# SCH_16pady.net
KiCad netlist of a schematic drawn in EasyEDA
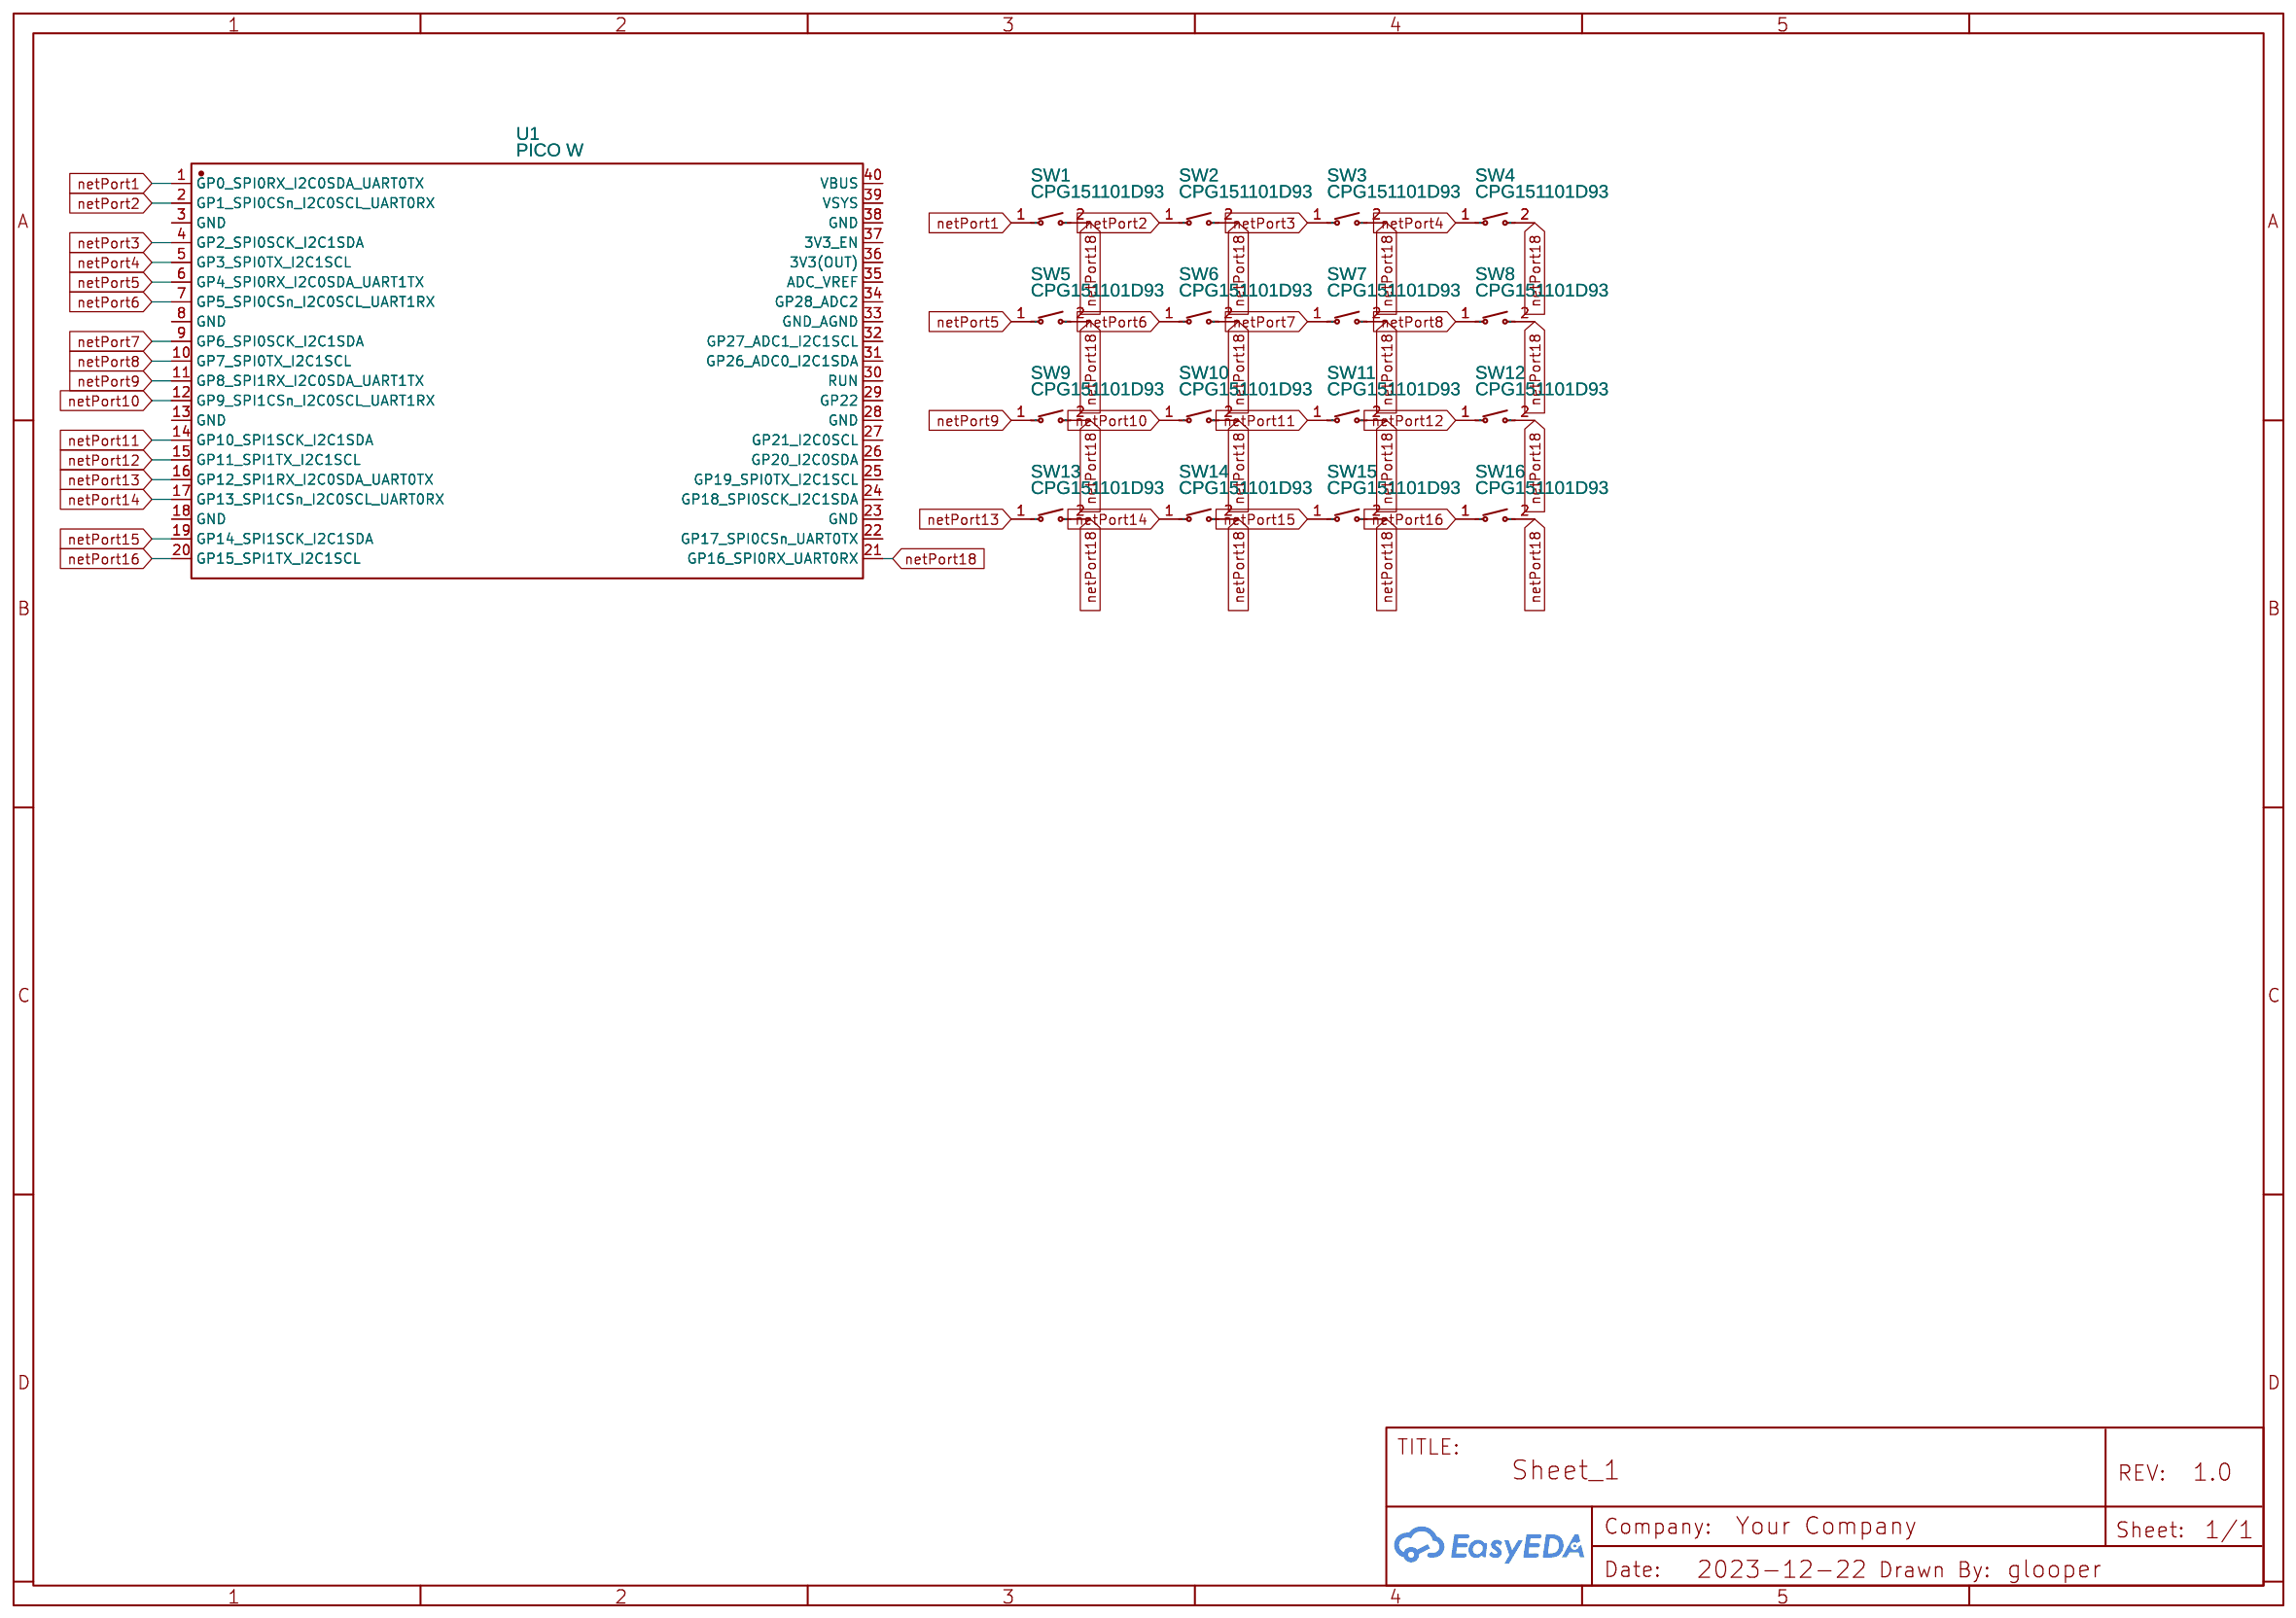
[diagram p0: schematic sheet]

(export (version "E")
  (design (tool "Eeschema 10.0.6"))
  (components
    (comp (ref "SW1")
      (value "CPG151101D93")
      (fields (field (name "Manufacturer") "Kailh(凯华)"))
      (libsource (lib "") (part "CPG151101D93"))
    )
    (comp (ref "SW2")
      (value "CPG151101D93")
      (fields (field (name "Manufacturer") "Kailh(凯华)"))
      (libsource (lib "") (part "CPG151101D93"))
    )
    (comp (ref "SW3")
      (value "CPG151101D93")
      (fields (field (name "Manufacturer") "Kailh(凯华)"))
      (libsource (lib "") (part "CPG151101D93"))
    )
    (comp (ref "SW4")
      (value "CPG151101D93")
      (fields (field (name "Manufacturer") "Kailh(凯华)"))
      (libsource (lib "") (part "CPG151101D93"))
    )
    (comp (ref "SW5")
      (value "CPG151101D93")
      (fields (field (name "Manufacturer") "Kailh(凯华)"))
      (libsource (lib "") (part "CPG151101D93"))
    )
    (comp (ref "SW6")
      (value "CPG151101D93")
      (fields (field (name "Manufacturer") "Kailh(凯华)"))
      (libsource (lib "") (part "CPG151101D93"))
    )
    (comp (ref "SW7")
      (value "CPG151101D93")
      (fields (field (name "Manufacturer") "Kailh(凯华)"))
      (libsource (lib "") (part "CPG151101D93"))
    )
    (comp (ref "SW8")
      (value "CPG151101D93")
      (fields (field (name "Manufacturer") "Kailh(凯华)"))
      (libsource (lib "") (part "CPG151101D93"))
    )
    (comp (ref "SW9")
      (value "CPG151101D93")
      (fields (field (name "Manufacturer") "Kailh(凯华)"))
      (libsource (lib "") (part "CPG151101D93"))
    )
    (comp (ref "SW10")
      (value "CPG151101D93")
      (fields (field (name "Manufacturer") "Kailh(凯华)"))
      (libsource (lib "") (part "CPG151101D93"))
    )
    (comp (ref "SW11")
      (value "CPG151101D93")
      (fields (field (name "Manufacturer") "Kailh(凯华)"))
      (libsource (lib "") (part "CPG151101D93"))
    )
    (comp (ref "SW12")
      (value "CPG151101D93")
      (fields (field (name "Manufacturer") "Kailh(凯华)"))
      (libsource (lib "") (part "CPG151101D93"))
    )
    (comp (ref "SW13")
      (value "CPG151101D93")
      (fields (field (name "Manufacturer") "Kailh(凯华)"))
      (libsource (lib "") (part "CPG151101D93"))
    )
    (comp (ref "SW14")
      (value "CPG151101D93")
      (fields (field (name "Manufacturer") "Kailh(凯华)"))
      (libsource (lib "") (part "CPG151101D93"))
    )
    (comp (ref "SW15")
      (value "CPG151101D93")
      (fields (field (name "Manufacturer") "Kailh(凯华)"))
      (libsource (lib "") (part "CPG151101D93"))
    )
    (comp (ref "SW16")
      (value "CPG151101D93")
      (fields (field (name "Manufacturer") "Kailh(凯华)"))
      (libsource (lib "") (part "CPG151101D93"))
    )
    (comp (ref "U1")
      (value "PICO W")
      (fields (field (name "Manufacturer") "Raspberry Pi(树莓派)"))
      (libsource (lib "") (part "PICO W"))
    )
  )
  (nets
    (net (code "1") (name "netPort1") (class "Default")
      (node (ref "SW1") (pin "1") (pinfunction "1_1") (pintype "unspecified"))
      (node (ref "U1") (pin "1") (pinfunction "GP0_SPI0RX_I2C0SDA_UART0TX_1") (pintype "unspecified"))
    )
    (net (code "2") (name "netPort2") (class "Default")
      (node (ref "SW2") (pin "1") (pinfunction "1_1") (pintype "unspecified"))
      (node (ref "U1") (pin "2") (pinfunction "GP1_SPI0CSn_I2C0SCL_UART0RX_2") (pintype "unspecified"))
    )
    (net (code "3") (name "netPort3") (class "Default")
      (node (ref "SW3") (pin "1") (pinfunction "1_1") (pintype "unspecified"))
      (node (ref "U1") (pin "4") (pinfunction "GP2_SPI0SCK_I2C1SDA_4") (pintype "unspecified"))
    )
    (net (code "4") (name "netPort4") (class "Default")
      (node (ref "SW4") (pin "1") (pinfunction "1_1") (pintype "unspecified"))
      (node (ref "U1") (pin "5") (pinfunction "GP3_SPI0TX_I2C1SCL_5") (pintype "unspecified"))
    )
    (net (code "5") (name "netPort5") (class "Default")
      (node (ref "SW5") (pin "1") (pinfunction "1_1") (pintype "unspecified"))
      (node (ref "U1") (pin "6") (pinfunction "GP4_SPI0RX_I2C0SDA_UART1TX_6") (pintype "unspecified"))
    )
    (net (code "6") (name "netPort6") (class "Default")
      (node (ref "SW6") (pin "1") (pinfunction "1_1") (pintype "unspecified"))
      (node (ref "U1") (pin "7") (pinfunction "GP5_SPI0CSn_I2C0SCL_UART1RX_7") (pintype "unspecified"))
    )
    (net (code "7") (name "netPort7") (class "Default")
      (node (ref "SW7") (pin "1") (pinfunction "1_1") (pintype "unspecified"))
      (node (ref "U1") (pin "9") (pinfunction "GP6_SPI0SCK_I2C1SDA_9") (pintype "unspecified"))
    )
    (net (code "8") (name "netPort8") (class "Default")
      (node (ref "SW8") (pin "1") (pinfunction "1_1") (pintype "unspecified"))
      (node (ref "U1") (pin "10") (pinfunction "GP7_SPI0TX_I2C1SCL_10") (pintype "unspecified"))
    )
    (net (code "9") (name "netPort9") (class "Default")
      (node (ref "SW9") (pin "1") (pinfunction "1_1") (pintype "unspecified"))
      (node (ref "U1") (pin "11") (pinfunction "GP8_SPI1RX_I2C0SDA_UART1TX_11") (pintype "unspecified"))
    )
    (net (code "10") (name "netPort10") (class "Default")
      (node (ref "SW10") (pin "1") (pinfunction "1_1") (pintype "unspecified"))
      (node (ref "U1") (pin "12") (pinfunction "GP9_SPI1CSn_I2C0SCL_UART1RX_12") (pintype "unspecified"))
    )
    (net (code "11") (name "netPort11") (class "Default")
      (node (ref "SW11") (pin "1") (pinfunction "1_1") (pintype "unspecified"))
      (node (ref "U1") (pin "14") (pinfunction "GP10_SPI1SCK_I2C1SDA_14") (pintype "unspecified"))
    )
    (net (code "12") (name "netPort12") (class "Default")
      (node (ref "SW12") (pin "1") (pinfunction "1_1") (pintype "unspecified"))
      (node (ref "U1") (pin "15") (pinfunction "GP11_SPI1TX_I2C1SCL_15") (pintype "unspecified"))
    )
    (net (code "13") (name "netPort13") (class "Default")
      (node (ref "SW13") (pin "1") (pinfunction "1_1") (pintype "unspecified"))
      (node (ref "U1") (pin "16") (pinfunction "GP12_SPI1RX_I2C0SDA_UART0TX_16") (pintype "unspecified"))
    )
    (net (code "14") (name "netPort14") (class "Default")
      (node (ref "SW14") (pin "1") (pinfunction "1_1") (pintype "unspecified"))
      (node (ref "U1") (pin "17") (pinfunction "GP13_SPI1CSn_I2C0SCL_UART0RX_17") (pintype "unspecified"))
    )
    (net (code "15") (name "netPort15") (class "Default")
      (node (ref "SW15") (pin "1") (pinfunction "1_1") (pintype "unspecified"))
      (node (ref "U1") (pin "19") (pinfunction "GP14_SPI1SCK_I2C1SDA_19") (pintype "unspecified"))
    )
    (net (code "16") (name "netPort16") (class "Default")
      (node (ref "SW16") (pin "1") (pinfunction "1_1") (pintype "unspecified"))
      (node (ref "U1") (pin "20") (pinfunction "GP15_SPI1TX_I2C1SCL_20") (pintype "unspecified"))
    )
    (net (code "17") (name "netPort18") (class "Default")
      (node (ref "SW1") (pin "2") (pinfunction "2_2") (pintype "unspecified"))
      (node (ref "SW10") (pin "2") (pinfunction "2_2") (pintype "unspecified"))
      (node (ref "SW11") (pin "2") (pinfunction "2_2") (pintype "unspecified"))
      (node (ref "SW12") (pin "2") (pinfunction "2_2") (pintype "unspecified"))
      (node (ref "SW13") (pin "2") (pinfunction "2_2") (pintype "unspecified"))
      (node (ref "SW14") (pin "2") (pinfunction "2_2") (pintype "unspecified"))
      (node (ref "SW15") (pin "2") (pinfunction "2_2") (pintype "unspecified"))
      (node (ref "SW16") (pin "2") (pinfunction "2_2") (pintype "unspecified"))
      (node (ref "SW2") (pin "2") (pinfunction "2_2") (pintype "unspecified"))
      (node (ref "SW3") (pin "2") (pinfunction "2_2") (pintype "unspecified"))
      (node (ref "SW4") (pin "2") (pinfunction "2_2") (pintype "unspecified"))
      (node (ref "SW5") (pin "2") (pinfunction "2_2") (pintype "unspecified"))
      (node (ref "SW6") (pin "2") (pinfunction "2_2") (pintype "unspecified"))
      (node (ref "SW7") (pin "2") (pinfunction "2_2") (pintype "unspecified"))
      (node (ref "SW8") (pin "2") (pinfunction "2_2") (pintype "unspecified"))
      (node (ref "SW9") (pin "2") (pinfunction "2_2") (pintype "unspecified"))
      (node (ref "U1") (pin "21") (pinfunction "GP16_SPI0RX_UART0RX_21") (pintype "unspecified"))
    )
    (net (code "18") (name "unconnected-(U1-3V3(OUT)-Pad36)") (class "Default")
      (node (ref "U1") (pin "36") (pinfunction "3V3(OUT)_36") (pintype "unspecified"))
    )
    (net (code "19") (name "unconnected-(U1-3V3_EN-Pad37)") (class "Default")
      (node (ref "U1") (pin "37") (pinfunction "3V3_EN_37") (pintype "unspecified"))
    )
    (net (code "20") (name "unconnected-(U1-ADC_VREF-Pad35)") (class "Default")
      (node (ref "U1") (pin "35") (pinfunction "ADC_VREF_35") (pintype "unspecified"))
    )
    (net (code "21") (name "unconnected-(U1-GND-Pad3)") (class "Default")
      (node (ref "U1") (pin "3") (pinfunction "GND_3") (pintype "unspecified"))
    )
    (net (code "22") (name "unconnected-(U1-GND-Pad8)") (class "Default")
      (node (ref "U1") (pin "8") (pinfunction "GND_8") (pintype "unspecified"))
    )
    (net (code "23") (name "unconnected-(U1-GND-Pad13)") (class "Default")
      (node (ref "U1") (pin "13") (pinfunction "GND_13") (pintype "unspecified"))
    )
    (net (code "24") (name "unconnected-(U1-GND-Pad18)") (class "Default")
      (node (ref "U1") (pin "18") (pinfunction "GND_18") (pintype "unspecified"))
    )
    (net (code "25") (name "unconnected-(U1-GND-Pad23)") (class "Default")
      (node (ref "U1") (pin "23") (pinfunction "GND_23") (pintype "unspecified"))
    )
    (net (code "26") (name "unconnected-(U1-GND-Pad28)") (class "Default")
      (node (ref "U1") (pin "28") (pinfunction "GND_28") (pintype "unspecified"))
    )
    (net (code "27") (name "unconnected-(U1-GND-Pad38)") (class "Default")
      (node (ref "U1") (pin "38") (pinfunction "GND_38") (pintype "unspecified"))
    )
    (net (code "28") (name "unconnected-(U1-GND_AGND-Pad33)") (class "Default")
      (node (ref "U1") (pin "33") (pinfunction "GND_AGND_33") (pintype "unspecified"))
    )
    (net (code "29") (name "unconnected-(U1-GP17_SPI0CSn_UART0TX-Pad22)") (class "Default")
      (node (ref "U1") (pin "22") (pinfunction "GP17_SPI0CSn_UART0TX_22") (pintype "unspecified"))
    )
    (net (code "30") (name "unconnected-(U1-GP18_SPI0SCK_I2C1SDA-Pad24)") (class "Default")
      (node (ref "U1") (pin "24") (pinfunction "GP18_SPI0SCK_I2C1SDA_24") (pintype "unspecified"))
    )
    (net (code "31") (name "unconnected-(U1-GP19_SPI0TX_I2C1SCL-Pad25)") (class "Default")
      (node (ref "U1") (pin "25") (pinfunction "GP19_SPI0TX_I2C1SCL_25") (pintype "unspecified"))
    )
    (net (code "32") (name "unconnected-(U1-GP20_I2C0SDA-Pad26)") (class "Default")
      (node (ref "U1") (pin "26") (pinfunction "GP20_I2C0SDA_26") (pintype "unspecified"))
    )
    (net (code "33") (name "unconnected-(U1-GP21_I2C0SCL-Pad27)") (class "Default")
      (node (ref "U1") (pin "27") (pinfunction "GP21_I2C0SCL_27") (pintype "unspecified"))
    )
    (net (code "34") (name "unconnected-(U1-GP22-Pad29)") (class "Default")
      (node (ref "U1") (pin "29") (pinfunction "GP22_29") (pintype "unspecified"))
    )
    (net (code "35") (name "unconnected-(U1-GP26_ADC0_I2C1SDA-Pad31)") (class "Default")
      (node (ref "U1") (pin "31") (pinfunction "GP26_ADC0_I2C1SDA_31") (pintype "unspecified"))
    )
    (net (code "36") (name "unconnected-(U1-GP27_ADC1_I2C1SCL-Pad32)") (class "Default")
      (node (ref "U1") (pin "32") (pinfunction "GP27_ADC1_I2C1SCL_32") (pintype "unspecified"))
    )
    (net (code "37") (name "unconnected-(U1-GP28_ADC2-Pad34)") (class "Default")
      (node (ref "U1") (pin "34") (pinfunction "GP28_ADC2_34") (pintype "unspecified"))
    )
    (net (code "38") (name "unconnected-(U1-RUN-Pad30)") (class "Default")
      (node (ref "U1") (pin "30") (pinfunction "RUN_30") (pintype "unspecified"))
    )
    (net (code "39") (name "unconnected-(U1-VBUS-Pad40)") (class "Default")
      (node (ref "U1") (pin "40") (pinfunction "VBUS_40") (pintype "unspecified"))
    )
    (net (code "40") (name "unconnected-(U1-VSYS-Pad39)") (class "Default")
      (node (ref "U1") (pin "39") (pinfunction "VSYS_39") (pintype "unspecified"))
    )
  )
)
